# tool_psu.net
KiCad netlist of a schematic drawn in EAGLE
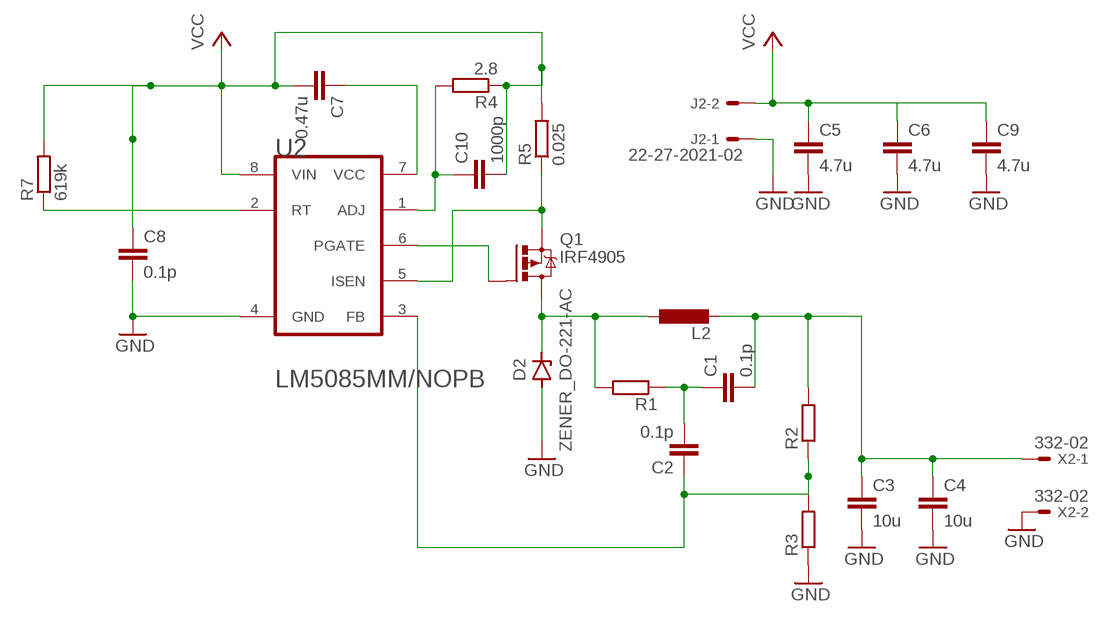
[diagram p0: schematic, sheet 1]

(export (version "E")
  (design (tool "Eeschema 10.0.6"))
  (components
    (comp (ref "C1")
      (value "0.1p")
      (footprint "eagle-import:C1206")
      (libsource (lib "eagle-import") (part "C-EUC1206"))
    )
    (comp (ref "C2")
      (value "0.1p")
      (footprint "eagle-import:C1206")
      (libsource (lib "eagle-import") (part "C-EUC1206"))
    )
    (comp (ref "C3")
      (value "10u")
      (footprint "eagle-import:C1206")
      (libsource (lib "eagle-import") (part "C-EUC1206"))
    )
    (comp (ref "C4")
      (value "10u")
      (footprint "eagle-import:C1206")
      (libsource (lib "eagle-import") (part "C-EUC1206"))
    )
    (comp (ref "C5")
      (value "4.7u")
      (footprint "eagle-import:C1206")
      (libsource (lib "eagle-import") (part "C-EUC1206"))
    )
    (comp (ref "C6")
      (value "4.7u")
      (footprint "eagle-import:C1206")
      (libsource (lib "eagle-import") (part "C-EUC1206"))
    )
    (comp (ref "C7")
      (value "0.47u")
      (footprint "eagle-import:C1206")
      (libsource (lib "eagle-import") (part "C-EUC1206"))
    )
    (comp (ref "C8")
      (value "0.1p")
      (footprint "eagle-import:C1206")
      (libsource (lib "eagle-import") (part "C-EUC1206"))
    )
    (comp (ref "C9")
      (value "4.7u")
      (footprint "eagle-import:C1206")
      (libsource (lib "eagle-import") (part "C-EUC1206"))
    )
    (comp (ref "C10")
      (value "1000p")
      (footprint "eagle-import:C1206")
      (libsource (lib "eagle-import") (part "C-EUC1206"))
    )
    (comp (ref "D2")
      (value "ZENER_DO-221-AC")
      (footprint "eagle-import:SODFL5226X110")
      (libsource (lib "eagle-import") (part "ZENERDO-221-AC_"))
    )
    (comp (ref "J2")
      (value "22-27-2021-02")
      (footprint "eagle-import:6410-02")
      (fields (field (name "MF") "MOLEX"))
      (libsource (lib "eagle-import") (part "22-?-0227-2021"))
    )
    (comp (ref "L2")
      (value "L-EU0204/5")
      (footprint "eagle-import:0204_5")
      (libsource (lib "eagle-import") (part "L-EU0204/5"))
    )
    (comp (ref "Q1")
      (value "IRF4905")
      (footprint "eagle-import:TO220BH")
      (libsource (lib "eagle-import") (part "IRF4905"))
    )
    (comp (ref "R1")
      (value "R-EU_M1206")
      (footprint "eagle-import:M1206")
      (libsource (lib "eagle-import") (part "R-EU_M1206"))
    )
    (comp (ref "R2")
      (value "R-EU_M1206")
      (footprint "eagle-import:M1206")
      (libsource (lib "eagle-import") (part "R-EU_M1206"))
    )
    (comp (ref "R3")
      (value "R-EU_M1206")
      (footprint "eagle-import:M1206")
      (libsource (lib "eagle-import") (part "R-EU_M1206"))
    )
    (comp (ref "R4")
      (value "2.8")
      (footprint "eagle-import:M1206")
      (libsource (lib "eagle-import") (part "R-EU_M1206"))
    )
    (comp (ref "R5")
      (value "0.025")
      (footprint "eagle-import:M1206")
      (libsource (lib "eagle-import") (part "R-EU_M1206"))
    )
    (comp (ref "R7")
      (value "619k")
      (footprint "eagle-import:M1206")
      (libsource (lib "eagle-import") (part "R-EU_M1206"))
    )
    (comp (ref "U2")
      (value "TI_NATIONAL_SEMICONDUCTOR_LM5085MM-NOPBTI_NATIONAL_SEMICONDUCTOR_LM5085MM-NOPB_0_0")
      (footprint "eagle-import:TI_NATIONAL_SEMICONDUCTOR_LM5085MM-NOPB_0")
      (fields (field (name "MF") "TI National Semiconductor") (field (name "MPN") "LM5085MM/NOPB"))
      (libsource (lib "eagle-import") (part "TI_NATIONAL_SEMICONDUCTOR_LM5085MM-NOPBTI_NATIONAL_SEMICONDUCTOR_LM5085MM-NOPB_0_0"))
    )
    (comp (ref "X2")
      (value "332-02")
      (footprint "eagle-import:332-02")
      (libsource (lib "eagle-import") (part "332-02"))
    )
  )
  (nets
    (net (code "1") (name "GND") (class "Default")
      (node (ref "C3") (pin "2") (pinfunction "2_2") (pintype "passive"))
      (node (ref "C4") (pin "2") (pinfunction "2_2") (pintype "passive"))
      (node (ref "C5") (pin "2") (pinfunction "2_2") (pintype "passive"))
      (node (ref "C6") (pin "2") (pinfunction "2_2") (pintype "passive"))
      (node (ref "C8") (pin "2") (pinfunction "2_2") (pintype "passive"))
      (node (ref "C9") (pin "2") (pinfunction "2_2") (pintype "passive"))
      (node (ref "D2") (pin "2") (pinfunction "A_2") (pintype "passive"))
      (node (ref "J2") (pin "1") (pinfunction "S_1") (pintype "passive"))
      (node (ref "R3") (pin "1") (pinfunction "1_1") (pintype "passive"))
      (node (ref "U2") (pin "4") (pinfunction "GND_4") (pintype "power_in"))
      (node (ref "X2") (pin "2") (pinfunction "S_2") (pintype "passive"))
    )
    (net (code "2") (name "Net-(C1-Pad1)") (class "Default")
      (node (ref "C1") (pin "1") (pinfunction "1_1") (pintype "passive"))
      (node (ref "C2") (pin "2") (pinfunction "2_2") (pintype "passive"))
      (node (ref "R1") (pin "1") (pinfunction "1_1") (pintype "passive"))
    )
    (net (code "3") (name "Net-(D2-C)") (class "Default")
      (node (ref "D2") (pin "1") (pinfunction "C_1") (pintype "passive"))
      (node (ref "L2") (pin "1") (pinfunction "1_1") (pintype "passive"))
      (node (ref "Q1") (pin "D") (pinfunction "D_D") (pintype "passive"))
      (node (ref "R1") (pin "2") (pinfunction "2_2") (pintype "passive"))
    )
    (net (code "4") (name "Net-(U2-ADJ)") (class "Default")
      (node (ref "C10") (pin "1") (pinfunction "1_1") (pintype "passive"))
      (node (ref "R4") (pin "2") (pinfunction "2_2") (pintype "passive"))
      (node (ref "U2") (pin "1") (pinfunction "ADJ_1") (pintype "passive"))
    )
    (net (code "5") (name "Net-(U2-FB)") (class "Default")
      (node (ref "C2") (pin "1") (pinfunction "1_1") (pintype "passive"))
      (node (ref "R2") (pin "1") (pinfunction "1_1") (pintype "passive"))
      (node (ref "R3") (pin "2") (pinfunction "2_2") (pintype "passive"))
      (node (ref "U2") (pin "3") (pinfunction "FB_3") (pintype "passive"))
    )
    (net (code "6") (name "Net-(U2-ISEN)") (class "Default")
      (node (ref "Q1") (pin "S") (pinfunction "S_S") (pintype "passive"))
      (node (ref "R5") (pin "1") (pinfunction "1_1") (pintype "passive"))
      (node (ref "U2") (pin "5") (pinfunction "ISEN_5") (pintype "passive"))
    )
    (net (code "7") (name "Net-(U2-PGATE)") (class "Default")
      (node (ref "Q1") (pin "G") (pinfunction "G_G") (pintype "passive"))
      (node (ref "U2") (pin "6") (pinfunction "PGATE_6") (pintype "passive"))
    )
    (net (code "8") (name "Net-(U2-RT)") (class "Default")
      (node (ref "R7") (pin "1") (pinfunction "1_1") (pintype "passive"))
      (node (ref "U2") (pin "2") (pinfunction "RT_2") (pintype "passive"))
    )
    (net (code "9") (name "Net-(U2-VCC)") (class "Default")
      (node (ref "C7") (pin "1") (pinfunction "1_1") (pintype "passive"))
      (node (ref "U2") (pin "7") (pinfunction "VCC_7") (pintype "power_in"))
    )
    (net (code "10") (name "Net-(X2A-S)") (class "Default")
      (node (ref "C1") (pin "2") (pinfunction "2_2") (pintype "passive"))
      (node (ref "C3") (pin "1") (pinfunction "1_1") (pintype "passive"))
      (node (ref "C4") (pin "1") (pinfunction "1_1") (pintype "passive"))
      (node (ref "L2") (pin "2") (pinfunction "2_2") (pintype "passive"))
      (node (ref "R2") (pin "2") (pinfunction "2_2") (pintype "passive"))
      (node (ref "X2") (pin "1") (pinfunction "S_1") (pintype "passive"))
    )
    (net (code "11") (name "VCC") (class "Default")
      (node (ref "C10") (pin "2") (pinfunction "2_2") (pintype "passive"))
      (node (ref "C5") (pin "1") (pinfunction "1_1") (pintype "passive"))
      (node (ref "C7") (pin "2") (pinfunction "2_2") (pintype "passive"))
      (node (ref "C8") (pin "1") (pinfunction "1_1") (pintype "passive"))
      (node (ref "C9") (pin "1") (pinfunction "1_1") (pintype "passive"))
      (node (ref "J2") (pin "2") (pinfunction "S_2") (pintype "passive"))
      (node (ref "R4") (pin "1") (pinfunction "1_1") (pintype "passive"))
      (node (ref "R5") (pin "2") (pinfunction "2_2") (pintype "passive"))
      (node (ref "R7") (pin "2") (pinfunction "2_2") (pintype "passive"))
      (node (ref "U2") (pin "8") (pinfunction "VIN_8") (pintype "passive"))
    )
    (net (code "12") (name "unconnected-(C6-Pad1)") (class "Default")
      (node (ref "C6") (pin "1") (pinfunction "1_1") (pintype "passive"))
    )
  )
)
